# TCsolo_v1.net
KiCad netlist of a schematic drawn in EAGLE
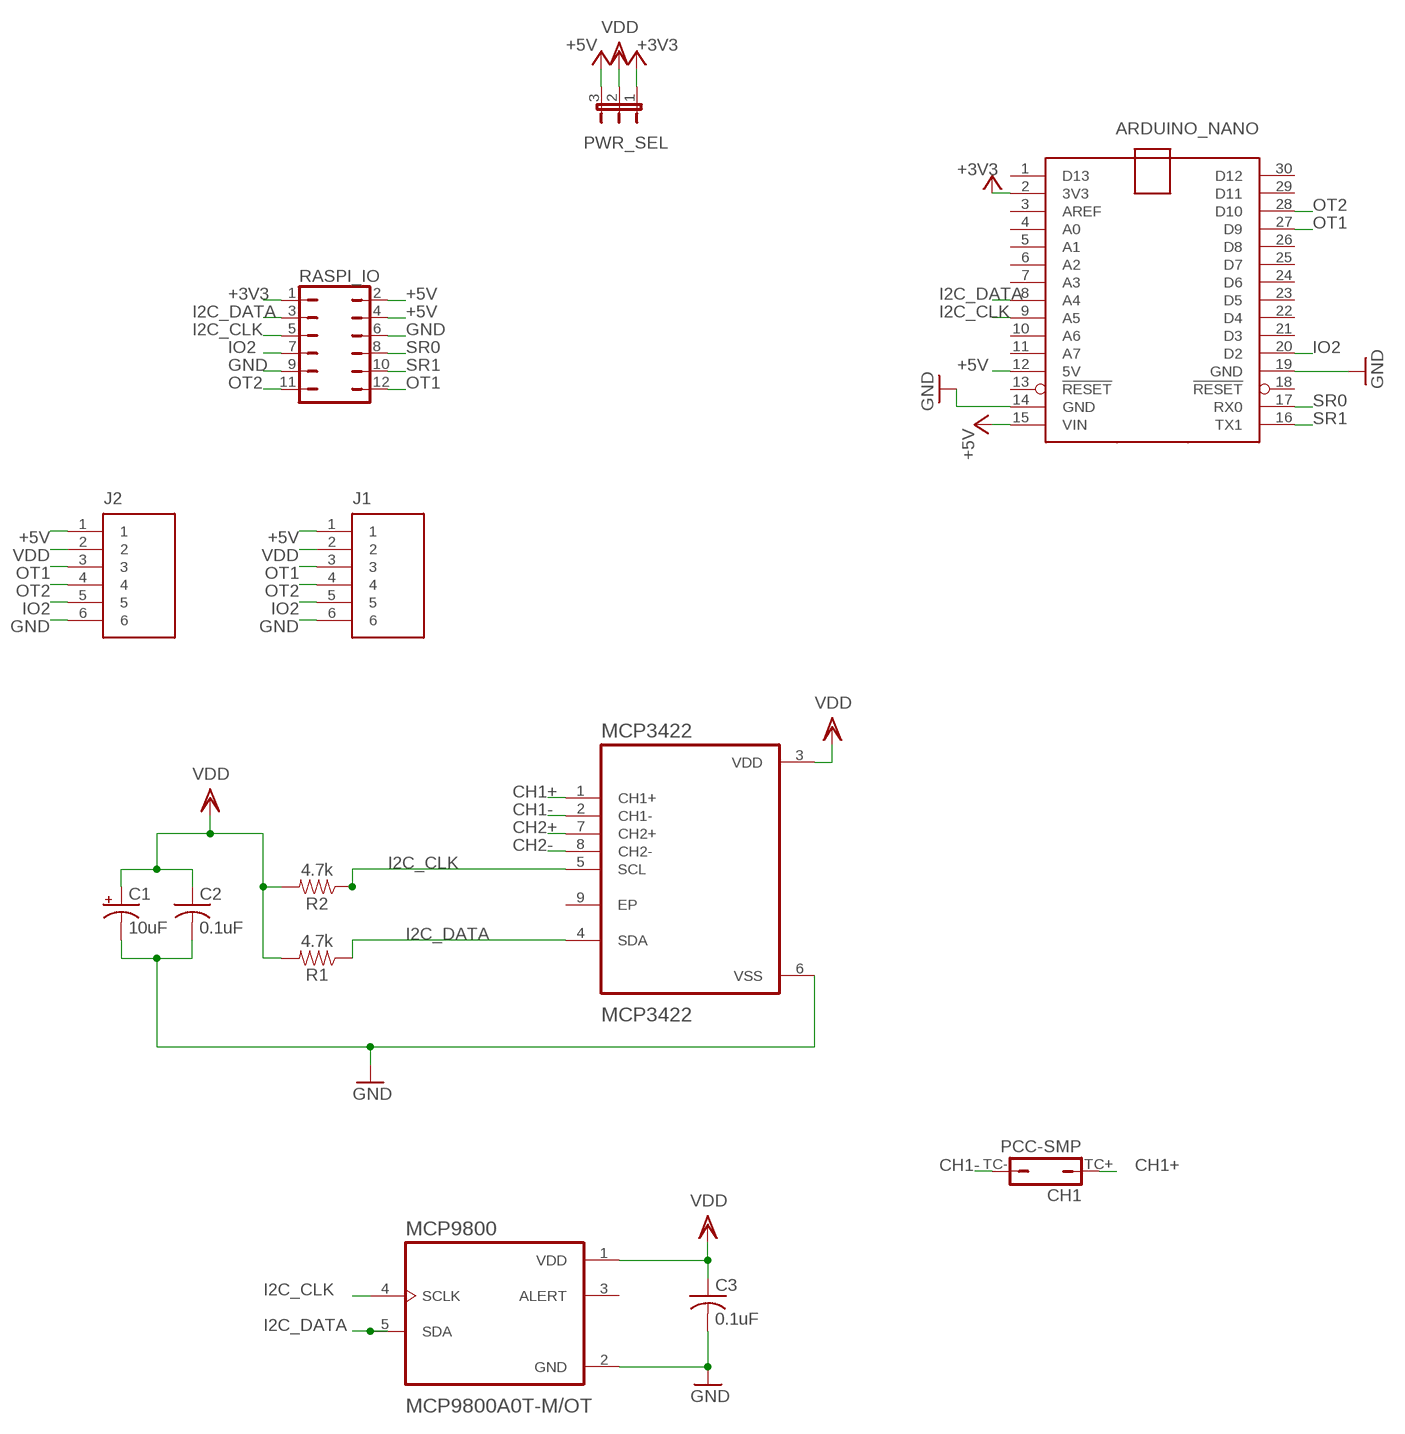
[diagram p0: schematic, sheet 1]

(export (version "E")
  (design (tool "Eeschema 10.0.6"))
  (components
    (comp (ref "ARDUINO_NANO")
      (value "ARDUINO_NANO")
      (footprint "eagle-import:ARDUINO_NANO")
      (libsource (lib "eagle-import") (part "ARDUINO_NANO"))
    )
    (comp (ref "C1")
      (value "10uF")
      (footprint "eagle-import:EIA3216")
      (libsource (lib "eagle-import") (part "10UF-POLAR-EIA3216-16V-10%(TANT)"))
    )
    (comp (ref "C2")
      (value "0.1uF")
      (footprint "eagle-import:C0805")
      (libsource (lib "eagle-import") (part "C-USC0805"))
    )
    (comp (ref "C3")
      (value "0.1uF")
      (footprint "eagle-import:C0805")
      (libsource (lib "eagle-import") (part "C-USC0805"))
    )
    (comp (ref "CH1")
      (value "PCC-SMP")
      (footprint "eagle-import:PCC-SMP")
      (libsource (lib "eagle-import") (part "PCC-SMP"))
    )
    (comp (ref "J1")
      (value "JST_6_PIN_VERTICAL")
      (footprint "eagle-import:JST-6-SMD-VERT-1.0MM")
      (libsource (lib "eagle-import") (part "JST_6_PIN_VERTICAL"))
    )
    (comp (ref "J2")
      (value "JST_6_PIN_VERTICAL")
      (footprint "eagle-import:JST-6-SMD-VERT-1.0MM")
      (libsource (lib "eagle-import") (part "JST_6_PIN_VERTICAL"))
    )
    (comp (ref "MCP3422")
      (value "MCP3422")
      (footprint "eagle-import:SON50P200X300X100-9N")
      (fields
        (field (name "DIGI-KEY_PART_NUMBER") "MCP3422A0-E/MC-ND")
        (field (name "MF") "Microchip")
        (field (name "MP") "MCP3422A0-E/MC")
      )
      (libsource (lib "eagle-import") (part "MCP3422A0-E/MC"))
    )
    (comp (ref "MCP9800")
      (value "MCP9800A0T-M/OT")
      (footprint "eagle-import:SOT95P270X145-5N")
      (fields (field (name "DIGI-KEY_PART_NUMBER") "MCP9800A0T-M/OTCT-ND") (field (name "MF") "Microchip"))
      (libsource (lib "eagle-import") (part "MCP9800A0T-M/OT"))
    )
    (comp (ref "PWR_SEL")
      (value "JP2E")
      (footprint "eagle-import:JP2")
      (libsource (lib "eagle-import") (part "JP2E"))
    )
    (comp (ref "R1")
      (value "4.7k")
      (footprint "eagle-import:0603")
      (libsource (lib "eagle-import") (part "4.7KOHM-0603-1/10W-1%"))
    )
    (comp (ref "R2")
      (value "4.7k")
      (footprint "eagle-import:0603")
      (libsource (lib "eagle-import") (part "4.7KOHM-0603-1/10W-1%"))
    )
    (comp (ref "RASPI_IO")
      (value "JP6Q")
      (footprint "eagle-import:JP6Q")
      (libsource (lib "eagle-import") (part "JP6Q"))
    )
  )
  (nets
    (net (code "1") (name "+3V3") (class "Default")
      (node (ref "ARDUINO_NANO") (pin "2") (pinfunction "3V3_2") (pintype "output"))
      (node (ref "PWR_SEL") (pin "1") (pinfunction "1_1") (pintype "passive"))
      (node (ref "RASPI_IO") (pin "1") (pinfunction "1_1") (pintype "passive"))
    )
    (net (code "2") (name "+5V") (class "Default")
      (node (ref "ARDUINO_NANO") (pin "12") (pinfunction "5V_12") (pintype "power_in"))
      (node (ref "ARDUINO_NANO") (pin "15") (pinfunction "VIN_15") (pintype "power_in"))
      (node (ref "J1") (pin "1") (pinfunction "1_1") (pintype "bidirectional"))
      (node (ref "J2") (pin "1") (pinfunction "1_1") (pintype "bidirectional"))
      (node (ref "PWR_SEL") (pin "3") (pinfunction "3_3") (pintype "passive"))
      (node (ref "RASPI_IO") (pin "2") (pinfunction "2_2") (pintype "passive"))
      (node (ref "RASPI_IO") (pin "4") (pinfunction "4_4") (pintype "passive"))
    )
    (net (code "3") (name "/CH1+") (class "Default")
      (node (ref "CH1") (pin "TC+") (pinfunction "1_TC+") (pintype "passive"))
      (node (ref "MCP3422") (pin "1") (pinfunction "CH1+_1") (pintype "input"))
    )
    (net (code "4") (name "/CH1-") (class "Default")
      (node (ref "CH1") (pin "TC-") (pinfunction "2_TC-") (pintype "passive"))
      (node (ref "MCP3422") (pin "2") (pinfunction "CH1-_2") (pintype "input"))
    )
    (net (code "5") (name "/CH2+") (class "Default")
      (node (ref "MCP3422") (pin "7") (pinfunction "CH2+_7") (pintype "input"))
    )
    (net (code "6") (name "/CH2-") (class "Default")
      (node (ref "MCP3422") (pin "8") (pinfunction "CH2-_8") (pintype "input"))
    )
    (net (code "7") (name "/I2C_CLK") (class "Default")
      (node (ref "ARDUINO_NANO") (pin "9") (pinfunction "A5_9") (pintype "bidirectional"))
      (node (ref "MCP3422") (pin "5") (pinfunction "SCL_5") (pintype "input"))
      (node (ref "MCP9800") (pin "4") (pinfunction "SCLK_4") (pintype "input"))
      (node (ref "R2") (pin "1") (pinfunction "1_1") (pintype "passive"))
      (node (ref "RASPI_IO") (pin "5") (pinfunction "5_5") (pintype "passive"))
    )
    (net (code "8") (name "/I2C_DATA") (class "Default")
      (node (ref "ARDUINO_NANO") (pin "8") (pinfunction "A4_8") (pintype "bidirectional"))
      (node (ref "MCP3422") (pin "4") (pinfunction "SDA_4") (pintype "bidirectional"))
      (node (ref "MCP9800") (pin "5") (pinfunction "SDA_5") (pintype "bidirectional"))
      (node (ref "R1") (pin "1") (pinfunction "1_1") (pintype "passive"))
      (node (ref "RASPI_IO") (pin "3") (pinfunction "3_3") (pintype "passive"))
    )
    (net (code "9") (name "/IO2") (class "Default")
      (node (ref "ARDUINO_NANO") (pin "20") (pinfunction "D2_20") (pintype "bidirectional"))
      (node (ref "J1") (pin "5") (pinfunction "5_5") (pintype "bidirectional"))
      (node (ref "J2") (pin "5") (pinfunction "5_5") (pintype "bidirectional"))
      (node (ref "RASPI_IO") (pin "7") (pinfunction "7_7") (pintype "passive"))
    )
    (net (code "10") (name "/OT1") (class "Default")
      (node (ref "ARDUINO_NANO") (pin "27") (pinfunction "D9_27") (pintype "bidirectional"))
      (node (ref "J1") (pin "3") (pinfunction "3_3") (pintype "bidirectional"))
      (node (ref "J2") (pin "3") (pinfunction "3_3") (pintype "bidirectional"))
      (node (ref "RASPI_IO") (pin "12") (pinfunction "12_12") (pintype "passive"))
    )
    (net (code "11") (name "/OT2") (class "Default")
      (node (ref "ARDUINO_NANO") (pin "28") (pinfunction "D10_28") (pintype "bidirectional"))
      (node (ref "J1") (pin "4") (pinfunction "4_4") (pintype "bidirectional"))
      (node (ref "J2") (pin "4") (pinfunction "4_4") (pintype "bidirectional"))
      (node (ref "RASPI_IO") (pin "11") (pinfunction "11_11") (pintype "passive"))
    )
    (net (code "12") (name "/SR0") (class "Default")
      (node (ref "ARDUINO_NANO") (pin "17") (pinfunction "RX0_17") (pintype "bidirectional"))
      (node (ref "RASPI_IO") (pin "8") (pinfunction "8_8") (pintype "passive"))
    )
    (net (code "13") (name "/SR1") (class "Default")
      (node (ref "ARDUINO_NANO") (pin "16") (pinfunction "TX1_16") (pintype "bidirectional"))
      (node (ref "RASPI_IO") (pin "10") (pinfunction "10_10") (pintype "passive"))
    )
    (net (code "14") (name "GND") (class "Default")
      (node (ref "ARDUINO_NANO") (pin "14") (pinfunction "GND_14") (pintype "power_in"))
      (node (ref "ARDUINO_NANO") (pin "19") (pinfunction "GND_19") (pintype "power_in"))
      (node (ref "C1") (pin "-") (pinfunction "-_-") (pintype "passive"))
      (node (ref "C2") (pin "2") (pinfunction "2_2") (pintype "passive"))
      (node (ref "C3") (pin "2") (pinfunction "2_2") (pintype "passive"))
      (node (ref "J1") (pin "6") (pinfunction "6_6") (pintype "bidirectional"))
      (node (ref "J2") (pin "6") (pinfunction "6_6") (pintype "bidirectional"))
      (node (ref "MCP3422") (pin "6") (pinfunction "VSS_6") (pintype "power_in"))
      (node (ref "MCP9800") (pin "2") (pinfunction "GND_2") (pintype "power_in"))
      (node (ref "RASPI_IO") (pin "6") (pinfunction "6_6") (pintype "passive"))
      (node (ref "RASPI_IO") (pin "9") (pinfunction "9_9") (pintype "passive"))
    )
    (net (code "15") (name "VDD") (class "Default")
      (node (ref "C1") (pin "+") (pinfunction "+_+") (pintype "passive"))
      (node (ref "C2") (pin "1") (pinfunction "1_1") (pintype "passive"))
      (node (ref "C3") (pin "1") (pinfunction "1_1") (pintype "passive"))
      (node (ref "J1") (pin "2") (pinfunction "2_2") (pintype "bidirectional"))
      (node (ref "J2") (pin "2") (pinfunction "2_2") (pintype "bidirectional"))
      (node (ref "MCP3422") (pin "3") (pinfunction "VDD_3") (pintype "power_in"))
      (node (ref "MCP9800") (pin "1") (pinfunction "VDD_1") (pintype "power_in"))
      (node (ref "PWR_SEL") (pin "2") (pinfunction "2_2") (pintype "passive"))
      (node (ref "R1") (pin "2") (pinfunction "2_2") (pintype "passive"))
      (node (ref "R2") (pin "2") (pinfunction "2_2") (pintype "passive"))
    )
    (net (code "16") (name "unconnected-(ARDUINO_NANO-A0-Pad4)") (class "Default")
      (node (ref "ARDUINO_NANO") (pin "4") (pinfunction "A0_4") (pintype "bidirectional"))
    )
    (net (code "17") (name "unconnected-(ARDUINO_NANO-A1-Pad5)") (class "Default")
      (node (ref "ARDUINO_NANO") (pin "5") (pinfunction "A1_5") (pintype "bidirectional"))
    )
    (net (code "18") (name "unconnected-(ARDUINO_NANO-A2-Pad6)") (class "Default")
      (node (ref "ARDUINO_NANO") (pin "6") (pinfunction "A2_6") (pintype "bidirectional"))
    )
    (net (code "19") (name "unconnected-(ARDUINO_NANO-A3-Pad7)") (class "Default")
      (node (ref "ARDUINO_NANO") (pin "7") (pinfunction "A3_7") (pintype "bidirectional"))
    )
    (net (code "20") (name "unconnected-(ARDUINO_NANO-A6-Pad10)") (class "Default")
      (node (ref "ARDUINO_NANO") (pin "10") (pinfunction "A6_10") (pintype "bidirectional"))
    )
    (net (code "21") (name "unconnected-(ARDUINO_NANO-A7-Pad11)") (class "Default")
      (node (ref "ARDUINO_NANO") (pin "11") (pinfunction "A7_11") (pintype "bidirectional"))
    )
    (net (code "22") (name "unconnected-(ARDUINO_NANO-AREF-Pad3)") (class "Default")
      (node (ref "ARDUINO_NANO") (pin "3") (pinfunction "AREF_3") (pintype "input"))
    )
    (net (code "23") (name "unconnected-(ARDUINO_NANO-D3-Pad21)") (class "Default")
      (node (ref "ARDUINO_NANO") (pin "21") (pinfunction "D3_21") (pintype "bidirectional"))
    )
    (net (code "24") (name "unconnected-(ARDUINO_NANO-D4-Pad22)") (class "Default")
      (node (ref "ARDUINO_NANO") (pin "22") (pinfunction "D4_22") (pintype "bidirectional"))
    )
    (net (code "25") (name "unconnected-(ARDUINO_NANO-D5-Pad23)") (class "Default")
      (node (ref "ARDUINO_NANO") (pin "23") (pinfunction "D5_23") (pintype "bidirectional"))
    )
    (net (code "26") (name "unconnected-(ARDUINO_NANO-D6-Pad24)") (class "Default")
      (node (ref "ARDUINO_NANO") (pin "24") (pinfunction "D6_24") (pintype "bidirectional"))
    )
    (net (code "27") (name "unconnected-(ARDUINO_NANO-D7-Pad25)") (class "Default")
      (node (ref "ARDUINO_NANO") (pin "25") (pinfunction "D7_25") (pintype "bidirectional"))
    )
    (net (code "28") (name "unconnected-(ARDUINO_NANO-D8-Pad26)") (class "Default")
      (node (ref "ARDUINO_NANO") (pin "26") (pinfunction "D8_26") (pintype "bidirectional"))
    )
    (net (code "29") (name "unconnected-(ARDUINO_NANO-D11-Pad29)") (class "Default")
      (node (ref "ARDUINO_NANO") (pin "29") (pinfunction "D11_29") (pintype "bidirectional"))
    )
    (net (code "30") (name "unconnected-(ARDUINO_NANO-D12-Pad30)") (class "Default")
      (node (ref "ARDUINO_NANO") (pin "30") (pinfunction "D12_30") (pintype "bidirectional"))
    )
    (net (code "31") (name "unconnected-(ARDUINO_NANO-D13-Pad1)") (class "Default")
      (node (ref "ARDUINO_NANO") (pin "1") (pinfunction "D13_1") (pintype "bidirectional"))
    )
    (net (code "32") (name "unconnected-(ARDUINO_NANO-~{RESET}-Pad13)") (class "Default")
      (node (ref "ARDUINO_NANO") (pin "13") (pinfunction "~{RESET}_13") (pintype "input"))
    )
    (net (code "33") (name "unconnected-(ARDUINO_NANO-~{RESET}-Pad18)") (class "Default")
      (node (ref "ARDUINO_NANO") (pin "18") (pinfunction "~{RESET}_18") (pintype "input"))
    )
    (net (code "34") (name "unconnected-(MCP3422-EP-Pad9)") (class "Default")
      (node (ref "MCP3422") (pin "9") (pinfunction "EP_9") (pintype "bidirectional"))
    )
    (net (code "35") (name "unconnected-(MCP9800-ALERT-Pad3)") (class "Default")
      (node (ref "MCP9800") (pin "3") (pinfunction "ALERT_3") (pintype "output"))
    )
  )
)
